# MelansonTech_Boost_PSU_IsolatedShuntAmp.net
KiCad netlist of a schematic drawn in Altium Designer
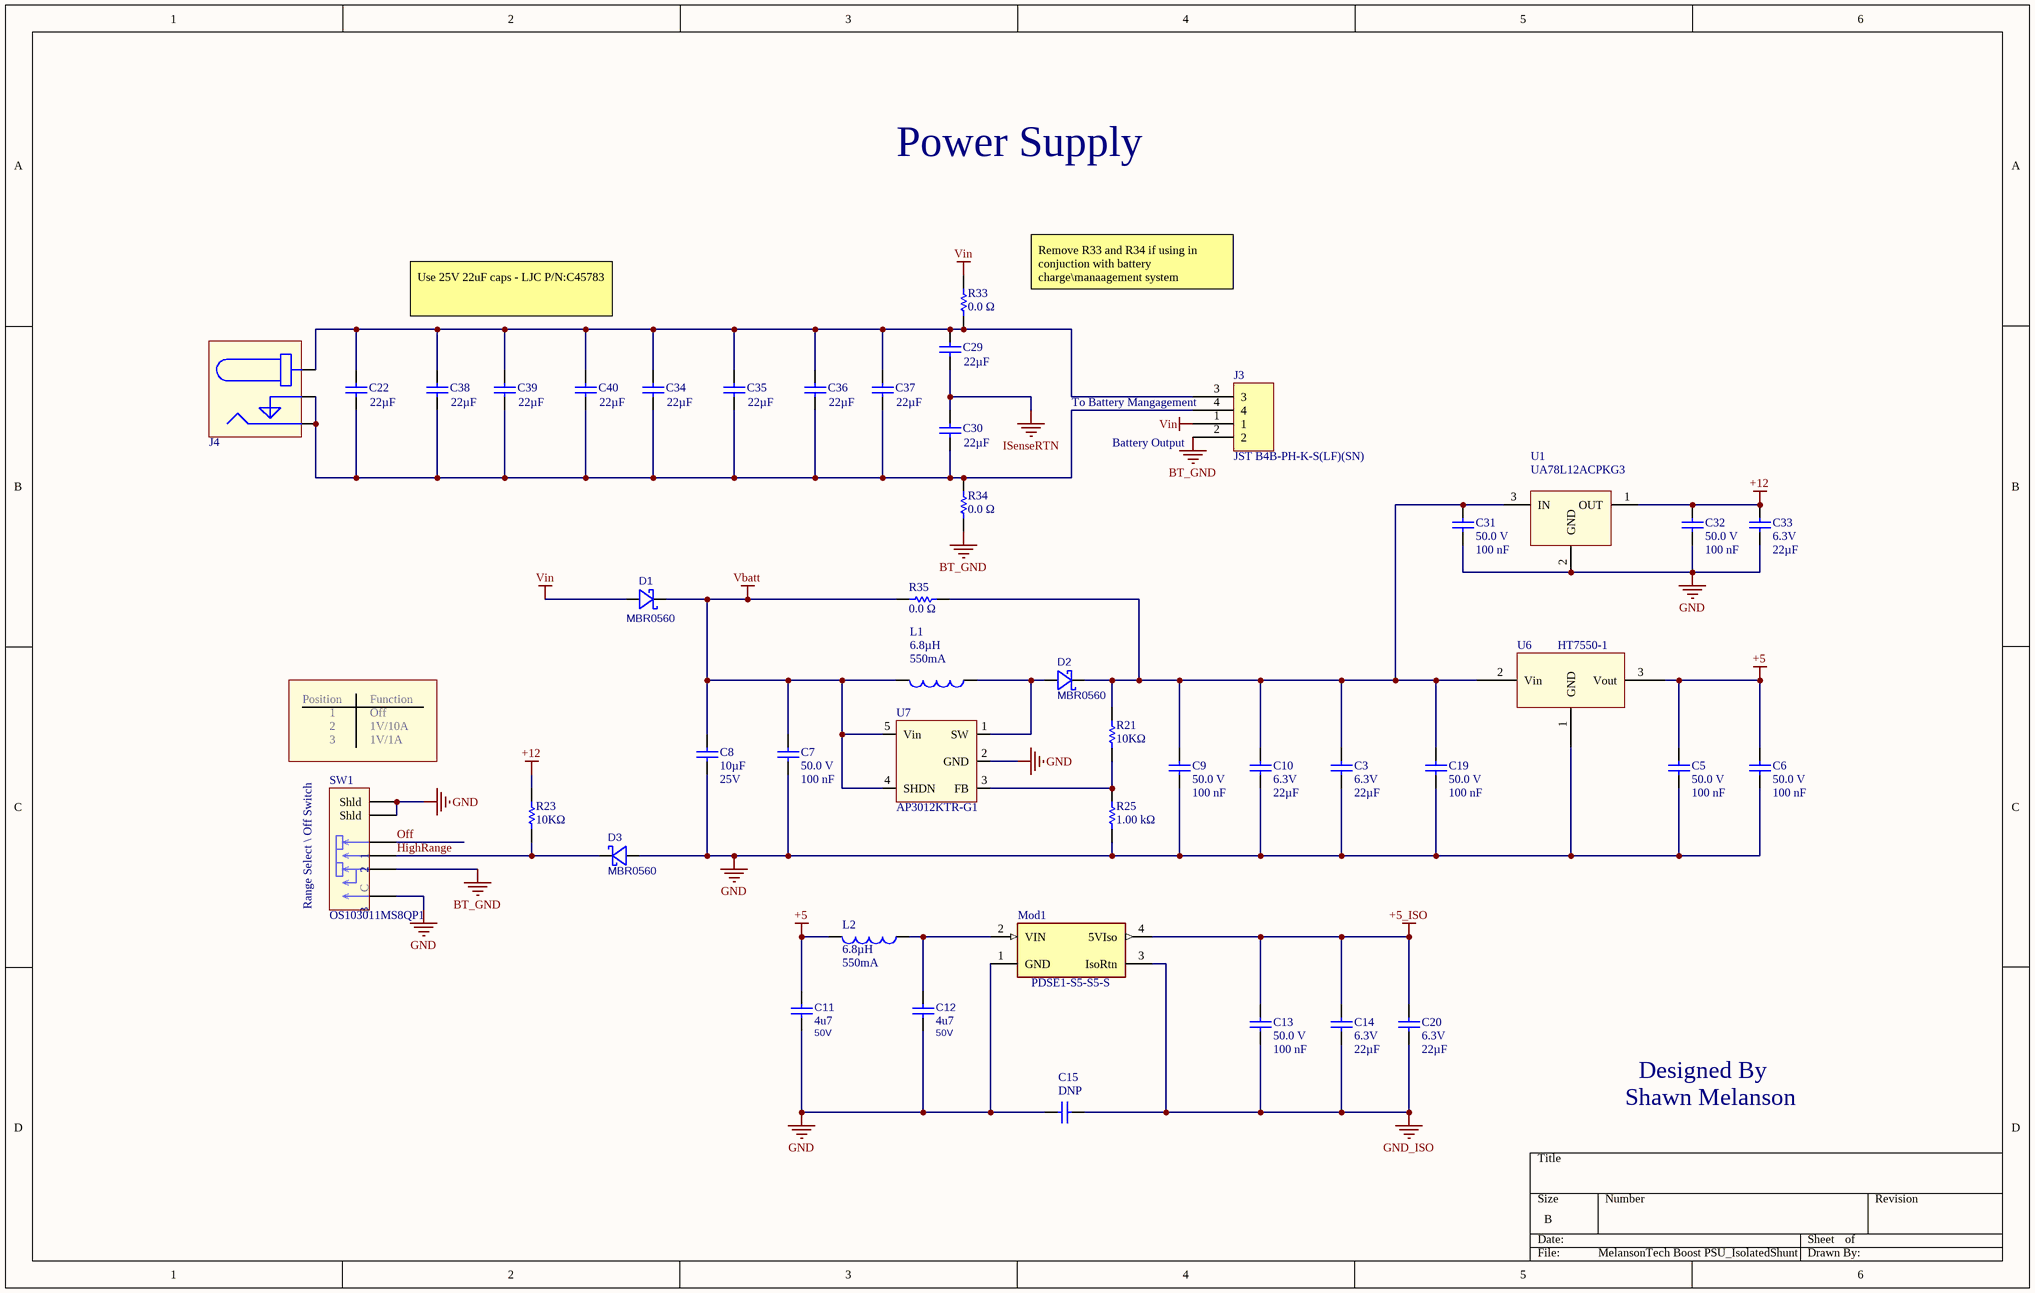
[diagram p0: MelansonTech Boost PSU_IsolatedShuntAmp.SchDoc]

(export (version "E")
  (design (tool "Eeschema 10.0.6"))
  (components
    (comp (ref "C3")
      (value "CL21A226MQQNNNE")
      (footprint "Cap,0805")
      (description "CAP CER 22UF 6.3V X5R 0805")
      (fields
        (field (name "MANUFACTURER") "Samsung Electro-Mechanics")
        (field (name "TOLERANCE") "±20%")
        (field (name "VOLTAGE - RATED") "6.3V")
        (field (name "CAPACITANCE") "22µF")
      )
      (libsource (lib "Master Mar2021") (part "Cap,0805,22uF,6.3V,X5R,±20%,CL21A226MQQNNNE"))
    )
    (comp (ref "C5")
      (value "CC0805KRX7R9BB104")
      (footprint "CAP, 0805, HD")
      (description "CAP CER 0.1UF 50V X7R 0805")
      (fields
        (field (name "VOLTAGE RATING (DC)") "50.0 V")
        (field (name "CAPACITANCE") "100 nF")
        (field (name "MANUFACTURER") "YAGEO")
      )
      (libsource (lib "Master Mar2024") (part "Cap,0805,100nf,50V,5%,CC0805KRX7R9BB104"))
    )
    (comp (ref "C6")
      (value "CC0805KRX7R9BB104")
      (footprint "CAP, 0805, HD")
      (description "CAP CER 0.1UF 50V X7R 0805")
      (fields
        (field (name "VOLTAGE RATING (DC)") "50.0 V")
        (field (name "CAPACITANCE") "100 nF")
        (field (name "MANUFACTURER") "YAGEO")
      )
      (libsource (lib "Master Mar2024") (part "Cap,0805,100nf,50V,5%,CC0805KRX7R9BB104"))
    )
    (comp (ref "C7")
      (value "CC0805KRX7R9BB104")
      (footprint "Cap,0805")
      (description "CAP CER 0.1UF 50V X7R 0805")
      (fields
        (field (name "VOLTAGE RATING (DC)") "50.0 V")
        (field (name "CAPACITANCE") "100 nF")
        (field (name "MANUFACTURER") "YAGEO")
      )
      (libsource (lib "Master Mar2024") (part "Cap,0805,100nf,50V,5%,CC0805KRX7R9BB104"))
    )
    (comp (ref "C8")
      (value "C3216X7R1E106K160AB")
      (footprint "Cap, 1206")
      (description "10µF ±10% 25V Ceramic Capacitor X7R 1206 (3216 Metric)")
      (fields
        (field (name "MANUFACTURER") "TDK Corporation")
        (field (name "TOLERANCE") "±10%")
        (field (name "CAPACITANCE") "10µF")
        (field (name "VOLTAGE - RATED") "25V")
      )
      (libsource (lib "Master DEC 2020") (part "CAP,1206,10uF,25V,C3216X7R1E106K160AB"))
    )
    (comp (ref "C9")
      (value "CC0805KRX7R9BB104")
      (footprint "CAP, 0805, HD")
      (description "CAP CER 0.1UF 50V X7R 0805")
      (fields
        (field (name "VOLTAGE RATING (DC)") "50.0 V")
        (field (name "CAPACITANCE") "100 nF")
        (field (name "MANUFACTURER") "YAGEO")
      )
      (libsource (lib "Master Mar2024") (part "Cap,0805,100nf,50V,5%,CC0805KRX7R9BB104"))
    )
    (comp (ref "C10")
      (value "CL21A226MQQNNNE")
      (footprint "Cap,0805")
      (description "CAP CER 22UF 6.3V X5R 0805")
      (fields
        (field (name "MANUFACTURER") "Samsung Electro-Mechanics")
        (field (name "TOLERANCE") "±20%")
        (field (name "VOLTAGE - RATED") "6.3V")
        (field (name "CAPACITANCE") "22µF")
      )
      (libsource (lib "Master Mar2021") (part "Cap,0805,22uF,6.3V,X5R,±20%,CL21A226MQQNNNE"))
    )
    (comp (ref "C11")
      (value "CL31B475KBHNNNE")
      (footprint "Cap, 1206")
      (description "Cap,SMD,MLCC,4u7,50V,X7R,10%,1206")
      (fields
        (field (name "MANUFACTURER") "Samsung")
        (field (name "TOLERANCE") "10%")
        (field (name "CAPACITANCE") "4u7")
        (field (name "VOLTAGE") "50V")
      )
      (libsource (lib "Master JULY2019") (part "Cap,1206,4.7uF,10%,50V,CL31B475KBHNNNE"))
    )
    (comp (ref "C12")
      (value "CL31B475KBHNNNE")
      (footprint "Cap, 1206")
      (description "Cap,SMD,MLCC,4u7,50V,X7R,10%,1206")
      (fields
        (field (name "MANUFACTURER") "Samsung")
        (field (name "TOLERANCE") "10%")
        (field (name "CAPACITANCE") "4u7")
        (field (name "VOLTAGE") "50V")
      )
      (libsource (lib "Master JULY2019") (part "Cap,1206,4.7uF,10%,50V,CL31B475KBHNNNE"))
    )
    (comp (ref "C13")
      (value "CC0805KRX7R9BB104")
      (footprint "Cap,0805")
      (description "CAP CER 0.1UF 50V X7R 0805")
      (fields
        (field (name "VOLTAGE RATING (DC)") "50.0 V")
        (field (name "CAPACITANCE") "100 nF")
        (field (name "MANUFACTURER") "YAGEO")
      )
      (libsource (lib "Master Mar2024") (part "Cap,0805,100nf,50V,5%,CC0805KRX7R9BB104"))
    )
    (comp (ref "C14")
      (value "CL21A226MQQNNNE")
      (footprint "Cap,0805")
      (description "CAP CER 22UF 6.3V X5R 0805")
      (fields
        (field (name "MANUFACTURER") "Samsung Electro-Mechanics")
        (field (name "TOLERANCE") "±20%")
        (field (name "VOLTAGE - RATED") "6.3V")
        (field (name "CAPACITANCE") "22µF")
      )
      (libsource (lib "Master Mar2021") (part "Cap,0805,22uF,6.3V,X5R,±20%,CL21A226MQQNNNE"))
    )
    (comp (ref "C15")
      (value "S102K33Y5PP63K5R")
      (footprint "Cap, 5mm Lead Spaceing, 4mm dai")
      (description "CAP CER 1000PF 2KV Y5P RADIAL")
      (fields (field (name "MANUFACTURER") "Vishay BC Components") (field (name "TOLERANCE") "±10%"))
      (libsource (lib "Master JULY2019") (part "Cap,TH,Ceramic,5mm Spacing,1nF,2kV, S102K33Y5PP63K5R"))
    )
    (comp (ref "C19")
      (value "CC0805KRX7R9BB104")
      (footprint "CAP, 0805, HD")
      (description "CAP CER 0.1UF 50V X7R 0805")
      (fields
        (field (name "VOLTAGE RATING (DC)") "50.0 V")
        (field (name "CAPACITANCE") "100 nF")
        (field (name "MANUFACTURER") "YAGEO")
      )
      (libsource (lib "Master Mar2024") (part "Cap,0805,100nf,50V,5%,CC0805KRX7R9BB104"))
    )
    (comp (ref "C20")
      (value "CL21A226MQQNNNE")
      (footprint "Cap,0805")
      (description "CAP CER 22UF 6.3V X5R 0805")
      (fields
        (field (name "MANUFACTURER") "Samsung Electro-Mechanics")
        (field (name "TOLERANCE") "±20%")
        (field (name "VOLTAGE - RATED") "6.3V")
        (field (name "CAPACITANCE") "22µF")
      )
      (libsource (lib "Master Mar2021") (part "Cap,0805,22uF,6.3V,X5R,±20%,CL21A226MQQNNNE"))
    )
    (comp (ref "C22")
      (value "CL21A226MQQNNNE")
      (footprint "Cap,0805")
      (description "CAP CER 22UF 6.3V X5R 0805")
      (fields
        (field (name "MANUFACTURER") "Samsung Electro-Mechanics")
        (field (name "TOLERANCE") "±20%")
        (field (name "CAPACITANCE") "22µF")
      )
      (libsource (lib "Master Mar2021") (part "Cap,0805,22uF,6.3V,X5R,±20%,CL21A226MQQNNNE"))
    )
    (comp (ref "C29")
      (value "CL21A226MQQNNNE")
      (footprint "Cap,0805")
      (description "CAP CER 22UF 6.3V X5R 0805")
      (fields
        (field (name "MANUFACTURER") "Samsung Electro-Mechanics")
        (field (name "TOLERANCE") "±20%")
        (field (name "CAPACITANCE") "22µF")
      )
      (libsource (lib "Master Mar2021") (part "Cap,0805,22uF,6.3V,X5R,±20%,CL21A226MQQNNNE"))
    )
    (comp (ref "C30")
      (value "CL21A226MQQNNNE")
      (footprint "Cap,0805")
      (description "CAP CER 22UF 6.3V X5R 0805")
      (fields
        (field (name "MANUFACTURER") "Samsung Electro-Mechanics")
        (field (name "TOLERANCE") "±20%")
        (field (name "CAPACITANCE") "22µF")
      )
      (libsource (lib "Master Mar2021") (part "Cap,0805,22uF,6.3V,X5R,±20%,CL21A226MQQNNNE"))
    )
    (comp (ref "C31")
      (value "CC0805KRX7R9BB104")
      (footprint "CAP, 0805, HD")
      (description "CAP CER 0.1UF 50V X7R 0805")
      (fields
        (field (name "VOLTAGE RATING (DC)") "50.0 V")
        (field (name "CAPACITANCE") "100 nF")
        (field (name "MANUFACTURER") "YAGEO")
      )
      (libsource (lib "Master Mar2024") (part "Cap,0805,100nf,50V,5%,CC0805KRX7R9BB104"))
    )
    (comp (ref "C32")
      (value "CC0805KRX7R9BB104")
      (footprint "CAP, 0805, HD")
      (description "CAP CER 0.1UF 50V X7R 0805")
      (fields
        (field (name "VOLTAGE RATING (DC)") "50.0 V")
        (field (name "CAPACITANCE") "100 nF")
        (field (name "MANUFACTURER") "YAGEO")
      )
      (libsource (lib "Master Mar2024") (part "Cap,0805,100nf,50V,5%,CC0805KRX7R9BB104"))
    )
    (comp (ref "C33")
      (value "CL21A226MQQNNNE")
      (footprint "Cap,0805")
      (description "CAP CER 22UF 6.3V X5R 0805")
      (fields
        (field (name "MANUFACTURER") "Samsung Electro-Mechanics")
        (field (name "TOLERANCE") "±20%")
        (field (name "VOLTAGE - RATED") "6.3V")
        (field (name "CAPACITANCE") "22µF")
      )
      (libsource (lib "Master Mar2021") (part "Cap,0805,22uF,6.3V,X5R,±20%,CL21A226MQQNNNE"))
    )
    (comp (ref "C34")
      (value "CL21A226MQQNNNE")
      (footprint "Cap,0805")
      (description "CAP CER 22UF 6.3V X5R 0805")
      (fields
        (field (name "MANUFACTURER") "Samsung Electro-Mechanics")
        (field (name "TOLERANCE") "±20%")
        (field (name "CAPACITANCE") "22µF")
      )
      (libsource (lib "Master Mar2021") (part "Cap,0805,22uF,6.3V,X5R,±20%,CL21A226MQQNNNE"))
    )
    (comp (ref "C35")
      (value "CL21A226MQQNNNE")
      (footprint "Cap,0805")
      (description "CAP CER 22UF 6.3V X5R 0805")
      (fields
        (field (name "MANUFACTURER") "Samsung Electro-Mechanics")
        (field (name "TOLERANCE") "±20%")
        (field (name "CAPACITANCE") "22µF")
      )
      (libsource (lib "Master Mar2021") (part "Cap,0805,22uF,6.3V,X5R,±20%,CL21A226MQQNNNE"))
    )
    (comp (ref "C36")
      (value "CL21A226MQQNNNE")
      (footprint "Cap,0805")
      (description "CAP CER 22UF 6.3V X5R 0805")
      (fields
        (field (name "MANUFACTURER") "Samsung Electro-Mechanics")
        (field (name "TOLERANCE") "±20%")
        (field (name "CAPACITANCE") "22µF")
      )
      (libsource (lib "Master Mar2021") (part "Cap,0805,22uF,6.3V,X5R,±20%,CL21A226MQQNNNE"))
    )
    (comp (ref "C37")
      (value "CL21A226MQQNNNE")
      (footprint "Cap,0805")
      (description "CAP CER 22UF 6.3V X5R 0805")
      (fields
        (field (name "MANUFACTURER") "Samsung Electro-Mechanics")
        (field (name "TOLERANCE") "±20%")
        (field (name "CAPACITANCE") "22µF")
      )
      (libsource (lib "Master Mar2021") (part "Cap,0805,22uF,6.3V,X5R,±20%,CL21A226MQQNNNE"))
    )
    (comp (ref "C38")
      (value "CL21A226MQQNNNE")
      (footprint "Cap,0805")
      (description "CAP CER 22UF 6.3V X5R 0805")
      (fields
        (field (name "MANUFACTURER") "Samsung Electro-Mechanics")
        (field (name "TOLERANCE") "±20%")
        (field (name "CAPACITANCE") "22µF")
      )
      (libsource (lib "Master Mar2021") (part "Cap,0805,22uF,6.3V,X5R,±20%,CL21A226MQQNNNE"))
    )
    (comp (ref "C39")
      (value "CL21A226MQQNNNE")
      (footprint "Cap,0805")
      (description "CAP CER 22UF 6.3V X5R 0805")
      (fields
        (field (name "MANUFACTURER") "Samsung Electro-Mechanics")
        (field (name "TOLERANCE") "±20%")
        (field (name "CAPACITANCE") "22µF")
      )
      (libsource (lib "Master Mar2021") (part "Cap,0805,22uF,6.3V,X5R,±20%,CL21A226MQQNNNE"))
    )
    (comp (ref "C40")
      (value "CL21A226MQQNNNE")
      (footprint "Cap,0805")
      (description "CAP CER 22UF 6.3V X5R 0805")
      (fields
        (field (name "MANUFACTURER") "Samsung Electro-Mechanics")
        (field (name "TOLERANCE") "±20%")
        (field (name "CAPACITANCE") "22µF")
      )
      (libsource (lib "Master Mar2021") (part "Cap,0805,22uF,6.3V,X5R,±20%,CL21A226MQQNNNE"))
    )
    (comp (ref "D1")
      (value "MBR0560")
      (footprint "SOD123")
      (description "Dio,Sig,Schtky,0.5A,60V,SOD123")
      (fields (field (name "MANUFACTURER") "MCC") (field (name "VOLTAGE") "60V"))
      (libsource (lib "Master DEC 2020") (part "Diode,SOD123,Shottky,60V,0.5A,MBR0560"))
    )
    (comp (ref "D2")
      (value "MBR0560")
      (footprint "SOD123")
      (description "Dio,Sig,Schtky,0.5A,60V,SOD123")
      (fields (field (name "MANUFACTURER") "MCC") (field (name "VOLTAGE") "60V"))
      (libsource (lib "Master DEC 2020") (part "Diode,SOD123,Shottky,60V,0.5A,MBR0560"))
    )
    (comp (ref "D3")
      (value "MBR0560")
      (footprint "SOD123")
      (description "Dio,Sig,Schtky,0.5A,60V,SOD123")
      (fields (field (name "MANUFACTURER") "MCC") (field (name "VOLTAGE") "60V"))
      (libsource (lib "Master DEC 2020") (part "Diode,SOD123,Shottky,60V,0.5A,MBR0560"))
    )
    (comp (ref "J3")
      (value "JST B4B-PH-K-S(LF)(SN)")
      (footprint "Conn, JST, 4 pin, 2mm spacing Right Angle")
      (description "PH Series 4 Position 2 mm Pitch Through Hole Crimp Top Entry Shrouded Header")
      (fields (field (name "MANUFACTURER PART NUMBER") "B4B-PH-K-S(LF)(SN)"))
      (libsource (lib "Master Nov2021") (part "Conntector, though hole, JST, 4pin, 2mm,B4B-PH-K-S(LF)(SN)"))
    )
    (comp (ref "J4")
      (value "PJ-002A")
      (footprint "Connector,Barrel,2.1mm,5.5mm,DC power Jack")
      (description "Power Barrel Connector Jack 2.10mm ID (0.083\"), 5.50mm OD (0.217\") Through Hole, Right Angle")
      (fields (field (name "MANUFACTURER") "CUI Inc."))
      (libsource (lib "Master Nov2021") (part "Connector,Barrel,ID 2.1mm,OD 5.5mm,Power Connect, PJ-002A"))
    )
    (comp (ref "L1")
      (value "MLZ2012N6R8LT000")
      (footprint "Ind, 0805")
      (description "FIXED IND 6.8UH 550MA 250 MOHM")
      (fields
        (field (name "MANUFACTURER") "TDK Corporation")
        (field (name "TOLERANCE") "±20%")
        (field (name "INDUCTANCE") "6.8µH")
        (field (name "CURRENT RATING (AMPS)") "550mA")
      )
      (libsource (lib "Master DEC 2020") (part "Ind,0805,6.8uH,550mA,0.25Ω, MLZ2012N6R8LT000"))
    )
    (comp (ref "L2")
      (value "MLZ2012N6R8LT000")
      (footprint "Ind, 0805")
      (description "FIXED IND 6.8UH 550MA 250 MOHM")
      (fields
        (field (name "MANUFACTURER") "TDK Corporation")
        (field (name "TOLERANCE") "±20%")
        (field (name "INDUCTANCE") "6.8µH")
        (field (name "CURRENT RATING (AMPS)") "550mA")
      )
      (libsource (lib "Master JULY2019") (part "Ind,0805,6.8uH,550mA,0.25Ω, MLZ2012N6R8LT000"))
    )
    (comp (ref "Mod1")
      (value "PDSE1-S5-S5-S")
      (footprint "CONV_PDSE1-S5-S5-S")
      (description "DC-DC ISOLATED, 1 W, 4.5-5.5 VDC")
      (fields (field (name "MANUFACTURER") "CUI Inc."))
      (libsource (lib "Master JULY2019") (part "Mod,PSU,4.5-5.5Vin,5Vout,1W, PDSE1-S5-S5-S"))
    )
    (comp (ref "R21")
      (value "Vishay / Dale CRCW080510K0FKTA")
      (footprint "res, 0805, HD")
      (description "RES SMD 10K OHM 1% 1/8W 0805")
      (fields (field (name "RESISTANCE") "10KΩ"))
      (libsource (lib "Master Mar2021") (part "Res,0805,10.0kΩ,1%,100 ppm,CRCW080510K0FKTA"))
    )
    (comp (ref "R23")
      (value "Vishay / Dale CRCW080510K0FKTA")
      (footprint "res, 0805, HD")
      (description "RES SMD 10K OHM 1% 1/8W 0805")
      (fields (field (name "RESISTANCE") "10KΩ"))
      (libsource (lib "Master JULY2019") (part "Res,0805,10.0kΩ,1%,100 ppm,CRCW080510K0FKTA"))
    )
    (comp (ref "R25")
      (value "Vishay CRCW08051K00JNEA")
      (footprint "res, 0805, HD")
      (description "Res Thick Film 0805 1K Ohm 5% 0.125W(1/8W) ±200ppm/C Molded SMD Automotive Paper T/R")
      (fields
        (field (name "MANUFACTURER PART NUMBER") "CRCW08051K00JNEA")
        (field (name "RESISTANCE") "1.00 kΩ")
      )
      (libsource (lib "Master DEC 2020") (part "Res,0805,1.00 kΩ,5%,200ppm,CRCW08051K00JNEA"))
    )
    (comp (ref "R33")
      (value "CR0805-J/-000ELF")
      (footprint "res, 0805, HD")
      (description "RES SMD 0 OHM JUMPER 1/8W 0805")
      (fields
        (field (name "TOLERANCE") "Jumper")
        (field (name "BASE PART NUMBER") "CR0805")
        (field (name "RESISTANCE") "0.0 Ω")
      )
      (libsource (lib "Master Nov2021") (part "Res,0805,0.0Ω,150V, CR0805-J/-000ELF"))
    )
    (comp (ref "R34")
      (value "CR0805-J/-000ELF")
      (footprint "res, 0805, HD")
      (description "RES SMD 0 OHM JUMPER 1/8W 0805")
      (fields
        (field (name "TOLERANCE") "Jumper")
        (field (name "BASE PART NUMBER") "CR0805")
        (field (name "RESISTANCE") "0.0 Ω")
      )
      (libsource (lib "Master Nov2021") (part "Res,0805,0.0Ω,150V, CR0805-J/-000ELF"))
    )
    (comp (ref "R35")
      (value "CR0805-J/-000ELF")
      (footprint "res, 0805, HD")
      (description "RES SMD 0 OHM JUMPER 1/8W 0805")
      (fields
        (field (name "TOLERANCE") "Jumper")
        (field (name "BASE PART NUMBER") "CR0805")
        (field (name "RESISTANCE") "0.0 Ω")
      )
      (libsource (lib "Master Nov2021") (part "Res,0805,0.0Ω,150V, CR0805-J/-000ELF"))
    )
    (comp (ref "SW1")
      (value "OS103011MS8QP1")
      (footprint "Switch,Slide,.SP3T, OS103011 -Side")
      (description "SWITCH SLIDE SP3T 100MA 12V")
      (fields (field (name "MANUFACTURER") "C&K"))
      (libsource (lib "Master Nov2021") (part "Switch,TH,Slide,SP3T,100MA,12V,OS103011MS8QP1"))
    )
    (comp (ref "U1")
      (value "UA78L12ACPKG3")
      (footprint "SOT89-3")
      (description "IC REG LINEAR 12V 100MA SOT89-3")
      (fields (field (name "MANUFACTURER") "Texas Instruments"))
      (libsource (lib "Master Nov2021") (part "Reg,Linear,Pos,Fixed,12Vout,27Vin,100mA,UA78L12ACPKG3"))
    )
    (comp (ref "U6")
      (value "HT7550-1")
      (footprint "SOT89-3")
      (description "LOW DROPOUT REGULATORS(LDO) POSITIVE FIXED 55MV @ 1MA 30V 5V 150MA SOT-89(SOT-89-3) ROHS")
      (fields
        (field (name "LCSC PART #") "C16106")
        (field (name "MANUFACTURER") "Holtek Semicon")
        (field (name "MFG P/N") "HT7550-1")
      )
      (libsource (lib "Master DEC 2020") (part "Reg,Linear,Fixed,SOT-89-3,30Vin,5Vout,150mA,HT7550-1"))
    )
    (comp (ref "U7")
      (value "AP3012KTR-G1")
      (footprint "SOT23-5")
      (description "IC REG BOOST ADJ 500MA SOT23-5")
      (fields (field (name "MANUFACTURER") "Diodes Incorporated") (field (name "MFG P/N") "AP3012KTR-G1"))
      (libsource (lib "Master DEC 2020") (part "Reg,Switching,Boost,2.6-16Vin,29Vout,0.5A, AP3012KTR-G1"))
    )
  )
  (nets
    (net (code "1") (name "+5") (class "Default")
      (node (ref "C11") (pin "2") (pintype "passive"))
      (node (ref "C5") (pin "2") (pinfunction "2_2") (pintype "passive"))
      (node (ref "C6") (pin "2") (pinfunction "2_2") (pintype "passive"))
      (node (ref "L2") (pin "2") (pinfunction "2_2") (pintype "passive"))
      (node (ref "U6") (pin "3") (pinfunction "Vout_3") (pintype "passive"))
    )
    (net (code "2") (name "+5_ISO") (class "Default")
      (node (ref "C13") (pin "2") (pinfunction "2_2") (pintype "passive"))
      (node (ref "C14") (pin "2") (pinfunction "2_2") (pintype "passive"))
      (node (ref "C20") (pin "2") (pinfunction "2_2") (pintype "passive"))
      (node (ref "Mod1") (pin "4") (pinfunction "5VIso_4") (pintype "output"))
    )
    (net (code "3") (name "+12") (class "Default")
      (node (ref "C32") (pin "2") (pinfunction "2_2") (pintype "passive"))
      (node (ref "C33") (pin "2") (pinfunction "2_2") (pintype "passive"))
      (node (ref "R23") (pin "1") (pinfunction "1_1") (pintype "passive"))
      (node (ref "U1") (pin "1") (pinfunction "OUT_1") (pintype "passive"))
    )
    (net (code "4") (name "/HighRange") (class "Default")
      (node (ref "D3") (pin "1") (pinfunction "C_1") (pintype "passive"))
      (node (ref "R23") (pin "2") (pinfunction "2_2") (pintype "passive"))
      (node (ref "SW1") (pin "3") (pinfunction "3_3") (pintype "passive"))
    )
    (net (code "5") (name "/Off") (class "Default")
      (node (ref "SW1") (pin "4") (pinfunction "4_4") (pintype "passive"))
    )
    (net (code "6") (name "BT_GND") (class "Default")
      (node (ref "J3") (pin "2") (pinfunction "2_2") (pintype "passive"))
      (node (ref "R34") (pin "2") (pinfunction "2_2") (pintype "passive"))
      (node (ref "SW1") (pin "2") (pinfunction "2_2") (pintype "passive"))
    )
    (net (code "7") (name "GND") (class "Default")
      (node (ref "C10") (pin "1") (pinfunction "1_1") (pintype "passive"))
      (node (ref "C11") (pin "1") (pintype "passive"))
      (node (ref "C12") (pin "1") (pintype "passive"))
      (node (ref "C15") (pin "2") (pinfunction "2_2") (pintype "passive"))
      (node (ref "C19") (pin "1") (pinfunction "1_1") (pintype "passive"))
      (node (ref "C3") (pin "1") (pinfunction "1_1") (pintype "passive"))
      (node (ref "C31") (pin "1") (pinfunction "1_1") (pintype "passive"))
      (node (ref "C32") (pin "1") (pinfunction "1_1") (pintype "passive"))
      (node (ref "C33") (pin "1") (pinfunction "1_1") (pintype "passive"))
      (node (ref "C5") (pin "1") (pinfunction "1_1") (pintype "passive"))
      (node (ref "C6") (pin "1") (pinfunction "1_1") (pintype "passive"))
      (node (ref "C7") (pin "1") (pinfunction "1_1") (pintype "passive"))
      (node (ref "C8") (pin "1") (pinfunction "1_1") (pintype "passive"))
      (node (ref "C9") (pin "1") (pinfunction "1_1") (pintype "passive"))
      (node (ref "D3") (pin "2") (pinfunction "A_2") (pintype "passive"))
      (node (ref "Mod1") (pin "1") (pinfunction "GND_1") (pintype "power_in"))
      (node (ref "R25") (pin "2") (pinfunction "2_2") (pintype "passive"))
      (node (ref "SW1") (pin "1") (pinfunction "1_1") (pintype "passive"))
      (node (ref "SW1") (pin "5") (pinfunction "Shld_5") (pintype "passive"))
      (node (ref "SW1") (pin "6") (pinfunction "Shld_6") (pintype "passive"))
      (node (ref "U1") (pin "2") (pinfunction "GND_2") (pintype "passive"))
      (node (ref "U6") (pin "1") (pinfunction "GND_1") (pintype "passive"))
      (node (ref "U7") (pin "2") (pinfunction "GND_2") (pintype "passive"))
    )
    (net (code "8") (name "GND_ISO") (class "Default")
      (node (ref "C13") (pin "1") (pinfunction "1_1") (pintype "passive"))
      (node (ref "C14") (pin "1") (pinfunction "1_1") (pintype "passive"))
      (node (ref "C15") (pin "1") (pinfunction "1_1") (pintype "passive"))
      (node (ref "C20") (pin "1") (pinfunction "1_1") (pintype "passive"))
      (node (ref "Mod1") (pin "3") (pinfunction "IsoRtn_3") (pintype "power_in"))
    )
    (net (code "9") (name "ISenseRTN") (class "Default")
      (node (ref "C29") (pin "1") (pinfunction "1_1") (pintype "passive"))
      (node (ref "C30") (pin "2") (pinfunction "2_2") (pintype "passive"))
    )
    (net (code "10") (name "Net-(C22-Pad1)") (class "Default")
      (node (ref "C22") (pin "1") (pinfunction "1_1") (pintype "passive"))
      (node (ref "C30") (pin "1") (pinfunction "1_1") (pintype "passive"))
      (node (ref "C34") (pin "1") (pinfunction "1_1") (pintype "passive"))
      (node (ref "C35") (pin "1") (pinfunction "1_1") (pintype "passive"))
      (node (ref "C36") (pin "1") (pinfunction "1_1") (pintype "passive"))
      (node (ref "C37") (pin "1") (pinfunction "1_1") (pintype "passive"))
      (node (ref "C38") (pin "1") (pinfunction "1_1") (pintype "passive"))
      (node (ref "C39") (pin "1") (pinfunction "1_1") (pintype "passive"))
      (node (ref "C40") (pin "1") (pinfunction "1_1") (pintype "passive"))
      (node (ref "J3") (pin "4") (pinfunction "4_4") (pintype "passive"))
      (node (ref "J4") (pin "2") (pinfunction "2_2") (pintype "passive"))
      (node (ref "J4") (pin "3") (pinfunction "3_3") (pintype "passive"))
      (node (ref "R34") (pin "1") (pinfunction "1_1") (pintype "passive"))
    )
    (net (code "11") (name "Net-(C22-Pad2)") (class "Default")
      (node (ref "C22") (pin "2") (pinfunction "2_2") (pintype "passive"))
      (node (ref "C29") (pin "2") (pinfunction "2_2") (pintype "passive"))
      (node (ref "C34") (pin "2") (pinfunction "2_2") (pintype "passive"))
      (node (ref "C35") (pin "2") (pinfunction "2_2") (pintype "passive"))
      (node (ref "C36") (pin "2") (pinfunction "2_2") (pintype "passive"))
      (node (ref "C37") (pin "2") (pinfunction "2_2") (pintype "passive"))
      (node (ref "C38") (pin "2") (pinfunction "2_2") (pintype "passive"))
      (node (ref "C39") (pin "2") (pinfunction "2_2") (pintype "passive"))
      (node (ref "C40") (pin "2") (pinfunction "2_2") (pintype "passive"))
      (node (ref "J3") (pin "3") (pinfunction "3_3") (pintype "passive"))
      (node (ref "J4") (pin "1") (pinfunction "1_1") (pintype "passive"))
      (node (ref "R33") (pin "2") (pinfunction "2_2") (pintype "passive"))
    )
    (net (code "12") (name "Net-(D2-A)") (class "Default")
      (node (ref "D2") (pin "2") (pinfunction "A_2") (pintype "passive"))
      (node (ref "L1") (pin "1") (pinfunction "1_1") (pintype "passive"))
      (node (ref "U7") (pin "1") (pinfunction "SW_1") (pintype "passive"))
    )
    (net (code "13") (name "Net-(D2-C)") (class "Default")
      (node (ref "C10") (pin "2") (pinfunction "2_2") (pintype "passive"))
      (node (ref "C19") (pin "2") (pinfunction "2_2") (pintype "passive"))
      (node (ref "C3") (pin "2") (pinfunction "2_2") (pintype "passive"))
      (node (ref "C31") (pin "2") (pinfunction "2_2") (pintype "passive"))
      (node (ref "C9") (pin "2") (pinfunction "2_2") (pintype "passive"))
      (node (ref "D2") (pin "1") (pinfunction "C_1") (pintype "passive"))
      (node (ref "R21") (pin "2") (pinfunction "2_2") (pintype "passive"))
      (node (ref "R35") (pin "2") (pinfunction "2_2") (pintype "passive"))
      (node (ref "U1") (pin "3") (pinfunction "IN_3") (pintype "passive"))
      (node (ref "U6") (pin "2") (pinfunction "Vin_2") (pintype "passive"))
    )
    (net (code "14") (name "Net-(Mod1-VIN)") (class "Default")
      (node (ref "C12") (pin "2") (pintype "passive"))
      (node (ref "L2") (pin "1") (pinfunction "1_1") (pintype "passive"))
      (node (ref "Mod1") (pin "2") (pinfunction "VIN_2") (pintype "input"))
    )
    (net (code "15") (name "Net-(U7-FB)") (class "Default")
      (node (ref "R21") (pin "1") (pinfunction "1_1") (pintype "passive"))
      (node (ref "R25") (pin "1") (pinfunction "1_1") (pintype "passive"))
      (node (ref "U7") (pin "3") (pinfunction "FB_3") (pintype "passive"))
    )
    (net (code "16") (name "Vbatt") (class "Default")
      (node (ref "C7") (pin "2") (pinfunction "2_2") (pintype "passive"))
      (node (ref "C8") (pin "2") (pinfunction "2_2") (pintype "passive"))
      (node (ref "D1") (pin "1") (pinfunction "C_1") (pintype "passive"))
      (node (ref "L1") (pin "2") (pinfunction "2_2") (pintype "passive"))
      (node (ref "R35") (pin "1") (pinfunction "1_1") (pintype "passive"))
      (node (ref "U7") (pin "4") (pinfunction "SHDN_4") (pintype "passive"))
      (node (ref "U7") (pin "5") (pinfunction "Vin_5") (pintype "passive"))
    )
    (net (code "17") (name "Vin") (class "Default")
      (node (ref "D1") (pin "2") (pinfunction "A_2") (pintype "passive"))
      (node (ref "J3") (pin "1") (pinfunction "1_1") (pintype "passive"))
      (node (ref "R33") (pin "1") (pinfunction "1_1") (pintype "passive"))
    )
  )
)
